# config.net
KiCad netlist of a schematic drawn in Altium Designer
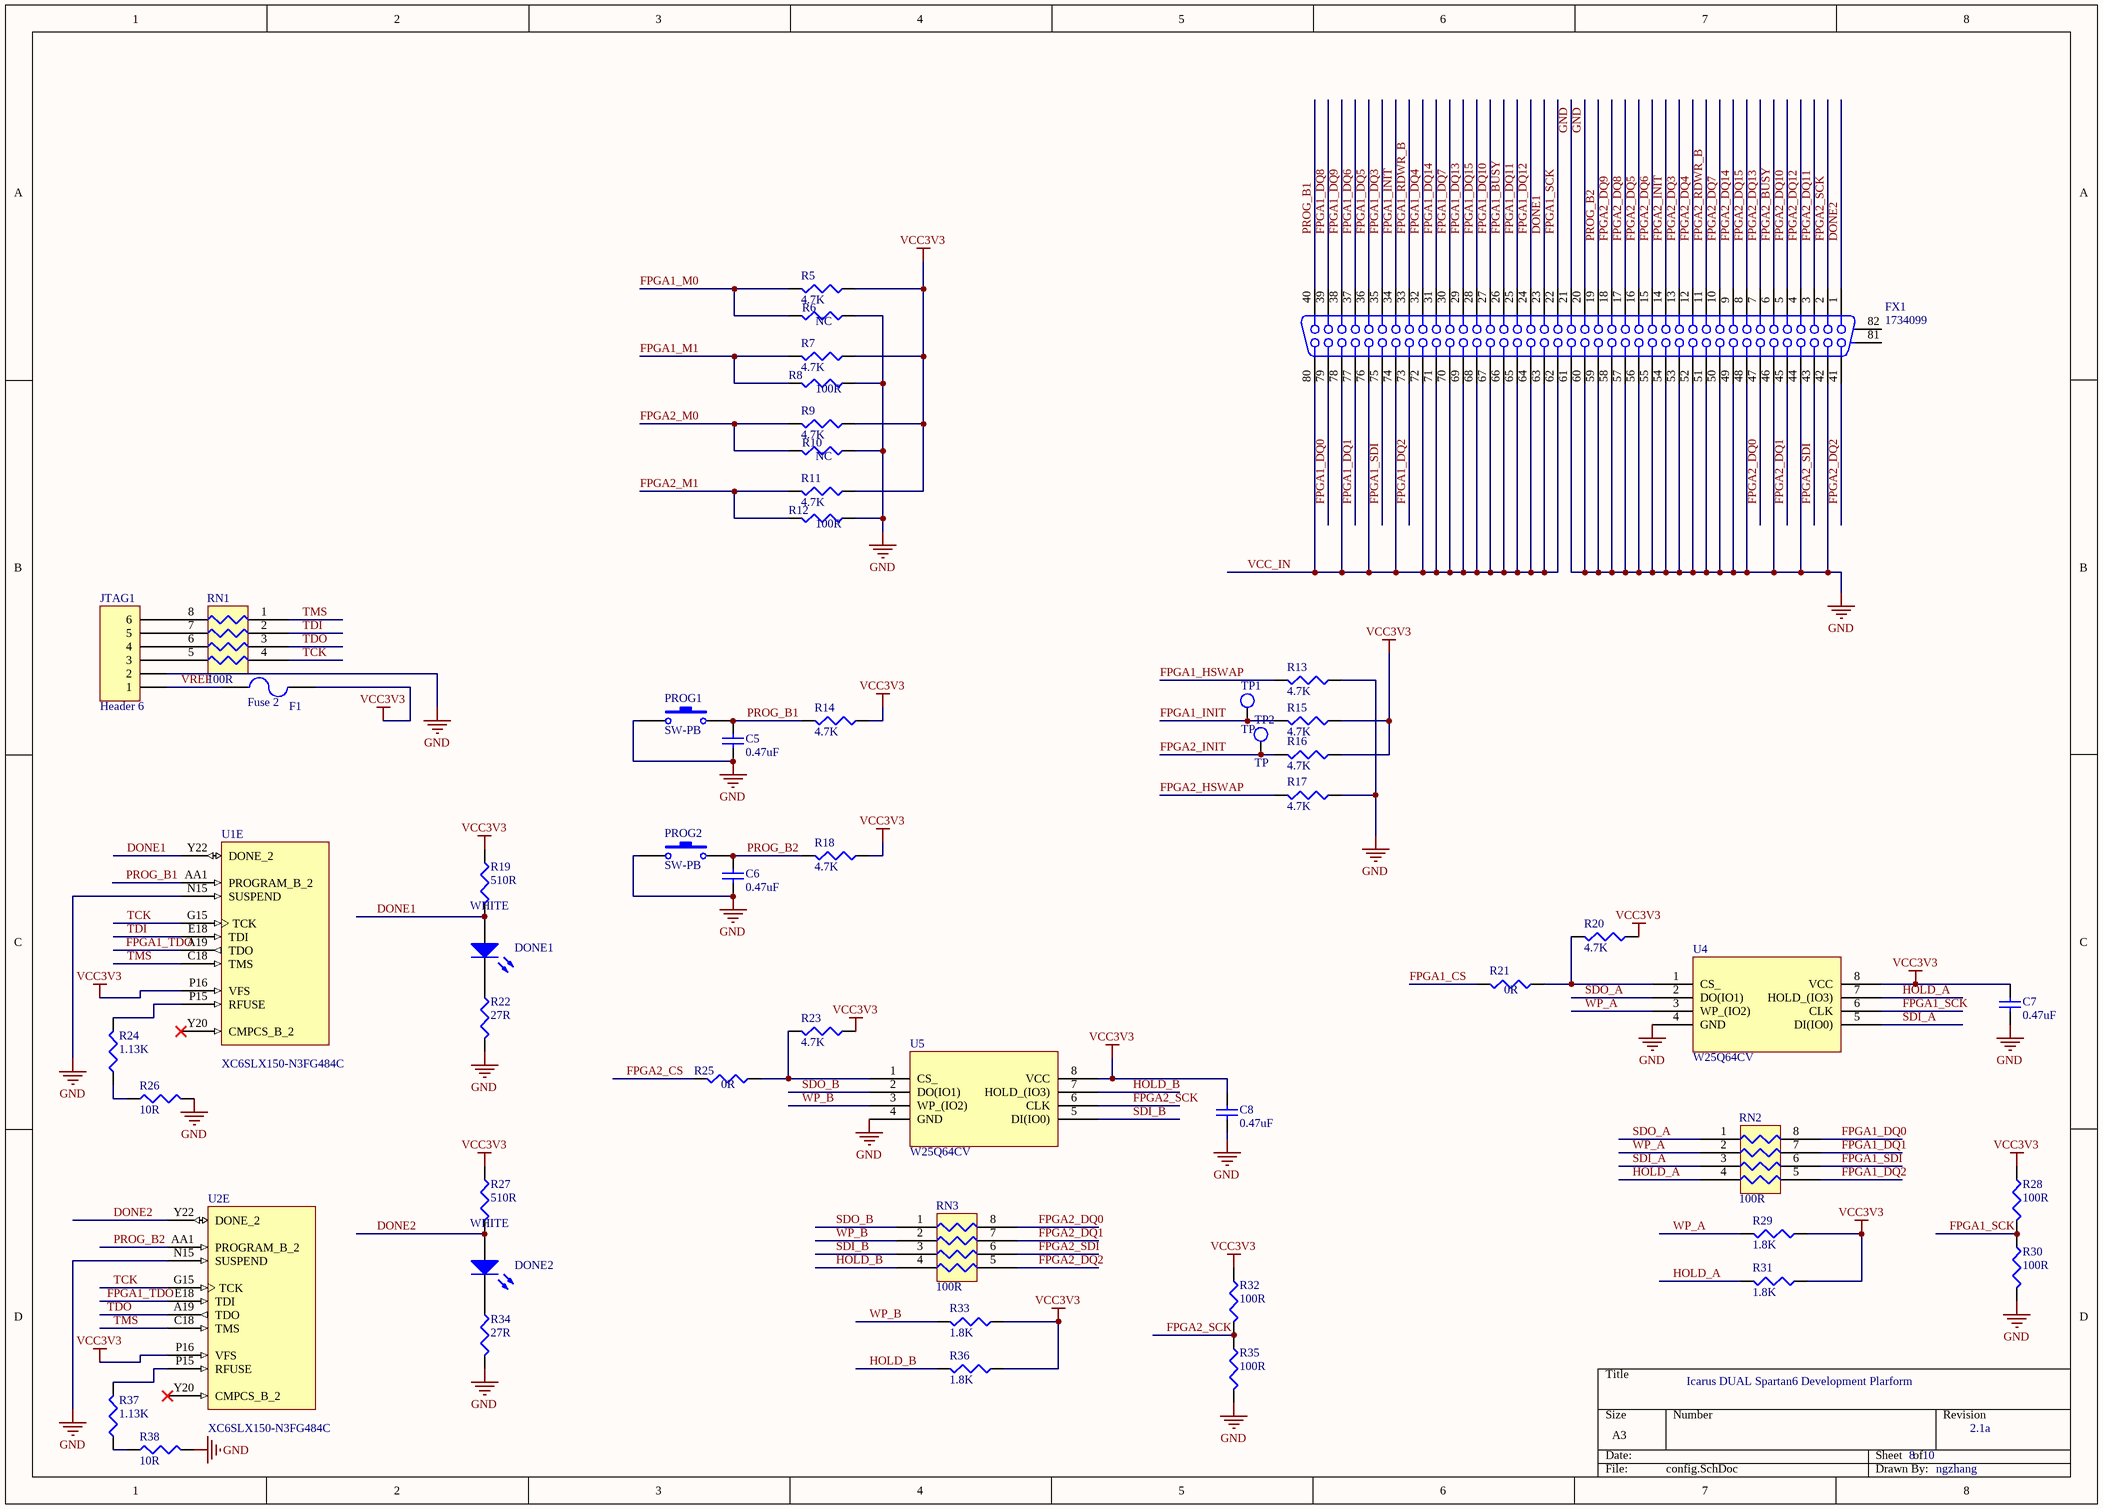
[diagram p0: config.SchDoc]

(export (version "E")
  (design (tool "Eeschema 10.0.6"))
  (components
    (comp (ref "C5")
      (value "0.47uF")
      (footprint "CAPC1005N")
      (description "Capacitor (Semiconductor SIM Model)")
      (fields (field (name "PUBLISHER") "Altium Limited"))
      (libsource (lib "Miscellaneous Devices") (part "Cap Semi"))
    )
    (comp (ref "C6")
      (value "0.47uF")
      (footprint "CAPC1005N")
      (description "Capacitor (Semiconductor SIM Model)")
      (fields (field (name "PUBLISHER") "Altium Limited"))
      (libsource (lib "Miscellaneous Devices") (part "Cap Semi"))
    )
    (comp (ref "C7")
      (value "0.47uF")
      (footprint "CAPC1005N")
      (description "Capacitor (Semiconductor SIM Model)")
      (fields (field (name "PUBLISHER") "Altium Limited"))
      (libsource (lib "Miscellaneous Devices") (part "Cap Semi"))
    )
    (comp (ref "C8")
      (value "0.47uF")
      (footprint "CAPC1005N")
      (description "Capacitor (Semiconductor SIM Model)")
      (fields (field (name "PUBLISHER") "Altium Limited"))
      (libsource (lib "Miscellaneous Devices") (part "Cap Semi"))
    )
    (comp (ref "DONE1")
      (value "WHITE")
      (footprint "CD1608-0603")
      (description "Typical BLUE SiC LED")
      (fields (field (name "PUBLISHER") "Altium Limited"))
      (libsource (lib "Miscellaneous Devices") (part "LED3"))
    )
    (comp (ref "DONE2")
      (value "WHITE")
      (footprint "CD1608-0603")
      (description "Typical BLUE SiC LED")
      (fields (field (name "PUBLISHER") "Altium Limited"))
      (libsource (lib "Miscellaneous Devices") (part "LED3"))
    )
    (comp (ref "F1")
      (value "Fuse 2")
      (footprint "RESC3216N")
      (description "Fuse")
      (fields (field (name "PUBLISHER") "Altium Limited"))
      (libsource (lib "Miscellaneous Devices") (part "Fuse 2"))
    )
    (comp (ref "FX1") (value "1734099") (footprint "1734099") (libsource (lib "S6_2") (part "1734099")))
    (comp (ref "JTAG1")
      (value "Header 6")
      (footprint "HDR1X6")
      (description "Header, 6-Pin")
      (fields (field (name "PUBLISHER") "Altium Limited"))
      (libsource (lib "Miscellaneous Connectors") (part "Header 6"))
    )
    (comp (ref "PROG1")
      (value "SW-PB")
      (footprint "SKQMA")
      (description "Switch")
      (fields (field (name "PUBLISHER") "Altium Limited"))
      (libsource (lib "Miscellaneous Devices") (part "SW-PB"))
    )
    (comp (ref "PROG2")
      (value "SW-PB")
      (footprint "SKQMA")
      (description "Switch")
      (fields (field (name "PUBLISHER") "Altium Limited"))
      (libsource (lib "Miscellaneous Devices") (part "SW-PB"))
    )
    (comp (ref "R5")
      (value "4.7K")
      (footprint "RESC1005N")
      (description "Resistor")
      (fields (field (name "PUBLISHER") "Altium Limited"))
      (libsource (lib "Miscellaneous Devices") (part "Res3"))
    )
    (comp (ref "R6")
      (value "NC")
      (footprint "RESC1005N")
      (description "Resistor")
      (fields (field (name "PUBLISHER") "Altium Limited"))
      (libsource (lib "Miscellaneous Devices") (part "Res3"))
    )
    (comp (ref "R7")
      (value "4.7K")
      (footprint "RESC1005N")
      (description "Resistor")
      (fields (field (name "PUBLISHER") "Altium Limited"))
      (libsource (lib "Miscellaneous Devices") (part "Res3"))
    )
    (comp (ref "R8")
      (value "100R")
      (footprint "RESC1005N")
      (description "Resistor")
      (fields (field (name "PUBLISHER") "Altium Limited"))
      (libsource (lib "Miscellaneous Devices") (part "Res3"))
    )
    (comp (ref "R9")
      (value "4.7K")
      (footprint "RESC1005N")
      (description "Resistor")
      (fields (field (name "PUBLISHER") "Altium Limited"))
      (libsource (lib "Miscellaneous Devices") (part "Res3"))
    )
    (comp (ref "R10")
      (value "NC")
      (footprint "RESC1005N")
      (description "Resistor")
      (fields (field (name "PUBLISHER") "Altium Limited"))
      (libsource (lib "Miscellaneous Devices") (part "Res3"))
    )
    (comp (ref "R11")
      (value "4.7K")
      (footprint "RESC1005N")
      (description "Resistor")
      (fields (field (name "PUBLISHER") "Altium Limited"))
      (libsource (lib "Miscellaneous Devices") (part "Res3"))
    )
    (comp (ref "R12")
      (value "100R")
      (footprint "RESC1005N")
      (description "Resistor")
      (fields (field (name "PUBLISHER") "Altium Limited"))
      (libsource (lib "Miscellaneous Devices") (part "Res3"))
    )
    (comp (ref "R13")
      (value "4.7K")
      (footprint "RESC1005N")
      (description "Resistor")
      (fields (field (name "PUBLISHER") "Altium Limited"))
      (libsource (lib "Miscellaneous Devices") (part "Res3"))
    )
    (comp (ref "R14")
      (value "4.7K")
      (footprint "RESC1005N")
      (description "Resistor")
      (fields (field (name "PUBLISHER") "Altium Limited"))
      (libsource (lib "Miscellaneous Devices") (part "Res3"))
    )
    (comp (ref "R15")
      (value "4.7K")
      (footprint "RESC1005N")
      (description "Resistor")
      (fields (field (name "PUBLISHER") "Altium Limited"))
      (libsource (lib "Miscellaneous Devices") (part "Res3"))
    )
    (comp (ref "R16")
      (value "4.7K")
      (footprint "RESC1005N")
      (description "Resistor")
      (fields (field (name "PUBLISHER") "Altium Limited"))
      (libsource (lib "Miscellaneous Devices") (part "Res3"))
    )
    (comp (ref "R17")
      (value "4.7K")
      (footprint "RESC1005N")
      (description "Resistor")
      (fields (field (name "PUBLISHER") "Altium Limited"))
      (libsource (lib "Miscellaneous Devices") (part "Res3"))
    )
    (comp (ref "R18")
      (value "4.7K")
      (footprint "RESC1005N")
      (description "Resistor")
      (fields (field (name "PUBLISHER") "Altium Limited"))
      (libsource (lib "Miscellaneous Devices") (part "Res3"))
    )
    (comp (ref "R19")
      (value "510R")
      (footprint "RESC1005N")
      (description "Resistor")
      (fields (field (name "PUBLISHER") "Altium Limited"))
      (libsource (lib "Miscellaneous Devices") (part "Res3"))
    )
    (comp (ref "R20")
      (value "4.7K")
      (footprint "RESC1005N")
      (description "Resistor")
      (fields (field (name "PUBLISHER") "Altium Limited"))
      (libsource (lib "Miscellaneous Devices") (part "Res3"))
    )
    (comp (ref "R21")
      (value "0R")
      (footprint "RESC1005N")
      (description "Resistor")
      (fields (field (name "PUBLISHER") "Altium Limited"))
      (libsource (lib "Miscellaneous Devices") (part "Res3"))
    )
    (comp (ref "R22")
      (value "27R")
      (footprint "RESC1005N")
      (description "Resistor")
      (fields (field (name "PUBLISHER") "Altium Limited"))
      (libsource (lib "Miscellaneous Devices") (part "Res3"))
    )
    (comp (ref "R23")
      (value "4.7K")
      (footprint "RESC1005N")
      (description "Resistor")
      (fields (field (name "PUBLISHER") "Altium Limited"))
      (libsource (lib "Miscellaneous Devices") (part "Res3"))
    )
    (comp (ref "R24")
      (value "1.13K")
      (footprint "RESC1608N")
      (description "Resistor")
      (fields (field (name "PUBLISHER") "Altium Limited"))
      (libsource (lib "Miscellaneous Devices") (part "Res3"))
    )
    (comp (ref "R25")
      (value "0R")
      (footprint "RESC1005N")
      (description "Resistor")
      (fields (field (name "PUBLISHER") "Altium Limited"))
      (libsource (lib "Miscellaneous Devices") (part "Res3"))
    )
    (comp (ref "R26")
      (value "10R")
      (footprint "RESC1608N")
      (description "Resistor")
      (fields (field (name "PUBLISHER") "Altium Limited"))
      (libsource (lib "Miscellaneous Devices") (part "Res3"))
    )
    (comp (ref "R27")
      (value "510R")
      (footprint "RESC1005N")
      (description "Resistor")
      (fields (field (name "PUBLISHER") "Altium Limited"))
      (libsource (lib "Miscellaneous Devices") (part "Res3"))
    )
    (comp (ref "R28")
      (value "100R")
      (footprint "RESC1005N")
      (description "Resistor")
      (fields (field (name "PUBLISHER") "Altium Limited"))
      (libsource (lib "Miscellaneous Devices") (part "Res3"))
    )
    (comp (ref "R29")
      (value "1.8K")
      (footprint "RESC1005N")
      (description "Resistor")
      (fields (field (name "PUBLISHER") "Altium Limited"))
      (libsource (lib "Miscellaneous Devices") (part "Res3"))
    )
    (comp (ref "R30")
      (value "100R")
      (footprint "RESC1005N")
      (description "Resistor")
      (fields (field (name "PUBLISHER") "Altium Limited"))
      (libsource (lib "Miscellaneous Devices") (part "Res3"))
    )
    (comp (ref "R31")
      (value "1.8K")
      (footprint "RESC1005N")
      (description "Resistor")
      (fields (field (name "PUBLISHER") "Altium Limited"))
      (libsource (lib "Miscellaneous Devices") (part "Res3"))
    )
    (comp (ref "R32")
      (value "100R")
      (footprint "RESC1005N")
      (description "Resistor")
      (fields (field (name "PUBLISHER") "Altium Limited"))
      (libsource (lib "Miscellaneous Devices") (part "Res3"))
    )
    (comp (ref "R33")
      (value "1.8K")
      (footprint "RESC1005N")
      (description "Resistor")
      (fields (field (name "PUBLISHER") "Altium Limited"))
      (libsource (lib "Miscellaneous Devices") (part "Res3"))
    )
    (comp (ref "R34")
      (value "27R")
      (footprint "RESC1005N")
      (description "Resistor")
      (fields (field (name "PUBLISHER") "Altium Limited"))
      (libsource (lib "Miscellaneous Devices") (part "Res3"))
    )
    (comp (ref "R35")
      (value "100R")
      (footprint "RESC1005N")
      (description "Resistor")
      (fields (field (name "PUBLISHER") "Altium Limited"))
      (libsource (lib "Miscellaneous Devices") (part "Res3"))
    )
    (comp (ref "R36")
      (value "1.8K")
      (footprint "RESC1005N")
      (description "Resistor")
      (fields (field (name "PUBLISHER") "Altium Limited"))
      (libsource (lib "Miscellaneous Devices") (part "Res3"))
    )
    (comp (ref "R37")
      (value "1.13K")
      (footprint "RESC1608N")
      (description "Resistor")
      (fields (field (name "PUBLISHER") "Altium Limited"))
      (libsource (lib "Miscellaneous Devices") (part "Res3"))
    )
    (comp (ref "R38")
      (value "10R")
      (footprint "RESC1608N")
      (description "Resistor")
      (fields (field (name "PUBLISHER") "Altium Limited"))
      (libsource (lib "Miscellaneous Devices") (part "Res3"))
    )
    (comp (ref "RN1") (value "100R") (footprint "EXBV8V") (libsource (lib "") (part "RES4PACK_1")))
    (comp (ref "RN2") (value "100R") (footprint "EXBV8V") (libsource (lib "S6") (part "RES4PACK")))
    (comp (ref "RN3") (value "100R") (footprint "EXBV8V") (libsource (lib "S6") (part "RES4PACK")))
    (comp (ref "TP1") (value "TP") (footprint "TP") (libsource (lib "S6") (part "TP")))
    (comp (ref "TP2") (value "TP") (footprint "TP") (libsource (lib "S6") (part "TP")))
    (comp (ref "U1")
      (value "XC6SLX150-N3FG484C")
      (footprint "FG484")
      (fields (field (name "PUBLISHER") "Altium Limited"))
      (libsource (lib "Xilinx Spartan-6") (part "XC6SLX150-N3FG484C"))
    )
    (comp (ref "U2")
      (value "XC6SLX150-N3FG484C")
      (footprint "FG484")
      (fields (field (name "PUBLISHER") "Altium Limited"))
      (libsource (lib "Xilinx Spartan-6") (part "XC6SLX150-N3FG484C"))
    )
    (comp (ref "U4") (value "W25Q64CV") (footprint "WSOP8") (libsource (lib "S6") (part "W25Q64CV")))
    (comp (ref "U5") (value "W25Q64CV") (footprint "WSOP8") (libsource (lib "S6") (part "W25Q64CV")))
  )
  (nets
    (net (code "1") (name "/DONE1") (class "Default")
      (node (ref "DONE1") (pin "1") (pinfunction "A_1") (pintype "passive"))
      (node (ref "FX1") (pin "23") (pinfunction "23_23") (pintype "passive"))
      (node (ref "R19") (pin "2") (pinfunction "2_2") (pintype "passive"))
      (node (ref "U1") (pin "Y22") (pinfunction "DONE_2_Y22") (pintype "bidirectional"))
    )
    (net (code "2") (name "/DONE2") (class "Default")
      (node (ref "DONE2") (pin "1") (pinfunction "A_1") (pintype "passive"))
      (node (ref "FX1") (pin "1") (pinfunction "1_1") (pintype "passive"))
      (node (ref "R27") (pin "2") (pinfunction "2_2") (pintype "passive"))
      (node (ref "U2") (pin "Y22") (pinfunction "DONE_2_Y22") (pintype "bidirectional"))
    )
    (net (code "3") (name "/FPGA1_BUSY") (class "Default")
      (node (ref "FX1") (pin "26") (pinfunction "26_26") (pintype "passive"))
    )
    (net (code "4") (name "/FPGA1_CS") (class "Default")
      (node (ref "R21") (pin "2") (pinfunction "2_2") (pintype "passive"))
    )
    (net (code "5") (name "/FPGA1_DQ0") (class "Default")
      (node (ref "FX1") (pin "79") (pinfunction "79_79") (pintype "passive"))
      (node (ref "RN2") (pin "8") (pinfunction "8_8") (pintype "power_in"))
    )
    (net (code "6") (name "/FPGA1_DQ1") (class "Default")
      (node (ref "FX1") (pin "77") (pinfunction "77_77") (pintype "passive"))
      (node (ref "RN2") (pin "7") (pinfunction "7_7") (pintype "power_in"))
    )
    (net (code "7") (name "/FPGA1_DQ2") (class "Default")
      (node (ref "FX1") (pin "73") (pinfunction "73_73") (pintype "passive"))
      (node (ref "RN2") (pin "5") (pinfunction "5_5") (pintype "power_in"))
    )
    (net (code "8") (name "/FPGA1_DQ3") (class "Default")
      (node (ref "FX1") (pin "35") (pinfunction "35_35") (pintype "passive"))
    )
    (net (code "9") (name "/FPGA1_DQ4") (class "Default")
      (node (ref "FX1") (pin "32") (pinfunction "32_32") (pintype "passive"))
    )
    (net (code "10") (name "/FPGA1_DQ5") (class "Default")
      (node (ref "FX1") (pin "36") (pinfunction "36_36") (pintype "passive"))
    )
    (net (code "11") (name "/FPGA1_DQ6") (class "Default")
      (node (ref "FX1") (pin "37") (pinfunction "37_37") (pintype "passive"))
    )
    (net (code "12") (name "/FPGA1_DQ7") (class "Default")
      (node (ref "FX1") (pin "30") (pinfunction "30_30") (pintype "passive"))
    )
    (net (code "13") (name "/FPGA1_DQ8") (class "Default")
      (node (ref "FX1") (pin "39") (pinfunction "39_39") (pintype "passive"))
    )
    (net (code "14") (name "/FPGA1_DQ9") (class "Default")
      (node (ref "FX1") (pin "38") (pinfunction "38_38") (pintype "passive"))
    )
    (net (code "15") (name "/FPGA1_DQ10") (class "Default")
      (node (ref "FX1") (pin "27") (pinfunction "27_27") (pintype "passive"))
    )
    (net (code "16") (name "/FPGA1_DQ11") (class "Default")
      (node (ref "FX1") (pin "25") (pinfunction "25_25") (pintype "passive"))
    )
    (net (code "17") (name "/FPGA1_DQ12") (class "Default")
      (node (ref "FX1") (pin "24") (pinfunction "24_24") (pintype "passive"))
    )
    (net (code "18") (name "/FPGA1_DQ13") (class "Default")
      (node (ref "FX1") (pin "29") (pinfunction "29_29") (pintype "passive"))
    )
    (net (code "19") (name "/FPGA1_DQ14") (class "Default")
      (node (ref "FX1") (pin "31") (pinfunction "31_31") (pintype "passive"))
    )
    (net (code "20") (name "/FPGA1_DQ15") (class "Default")
      (node (ref "FX1") (pin "28") (pinfunction "28_28") (pintype "passive"))
    )
    (net (code "21") (name "/FPGA1_HSWAP") (class "Default")
      (node (ref "R13") (pin "2") (pinfunction "2_2") (pintype "passive"))
    )
    (net (code "22") (name "/FPGA1_INIT") (class "Default")
      (node (ref "FX1") (pin "34") (pinfunction "34_34") (pintype "passive"))
      (node (ref "R15") (pin "2") (pinfunction "2_2") (pintype "passive"))
      (node (ref "TP1") (pin "1") (pinfunction "TP_1") (pintype "passive"))
    )
    (net (code "23") (name "/FPGA1_M0") (class "Default")
      (node (ref "R5") (pin "2") (pinfunction "2_2") (pintype "passive"))
      (node (ref "R6") (pin "2") (pinfunction "2_2") (pintype "passive"))
    )
    (net (code "24") (name "/FPGA1_M1") (class "Default")
      (node (ref "R7") (pin "2") (pinfunction "2_2") (pintype "passive"))
      (node (ref "R8") (pin "2") (pinfunction "2_2") (pintype "passive"))
    )
    (net (code "25") (name "/FPGA1_RDWR_B") (class "Default")
      (node (ref "FX1") (pin "33") (pinfunction "33_33") (pintype "passive"))
    )
    (net (code "26") (name "/FPGA1_SCK") (class "Default")
      (node (ref "FX1") (pin "22") (pinfunction "22_22") (pintype "passive"))
      (node (ref "R28") (pin "2") (pinfunction "2_2") (pintype "passive"))
      (node (ref "R30") (pin "1") (pinfunction "1_1") (pintype "passive"))
      (node (ref "U4") (pin "6") (pinfunction "CLK_6") (pintype "passive"))
    )
    (net (code "27") (name "/FPGA1_SDI") (class "Default")
      (node (ref "FX1") (pin "75") (pinfunction "75_75") (pintype "passive"))
      (node (ref "RN2") (pin "6") (pinfunction "6_6") (pintype "power_in"))
    )
    (net (code "28") (name "/FPGA1_TDO") (class "Default")
      (node (ref "U1") (pin "A19") (pinfunction "TDO_A19") (pintype "output"))
      (node (ref "U2") (pin "E18") (pinfunction "TDI_E18") (pintype "input"))
    )
    (net (code "29") (name "/FPGA2_BUSY") (class "Default")
      (node (ref "FX1") (pin "6") (pinfunction "6_6") (pintype "passive"))
    )
    (net (code "30") (name "/FPGA2_CS") (class "Default")
      (node (ref "R25") (pin "2") (pinfunction "2_2") (pintype "passive"))
    )
    (net (code "31") (name "/FPGA2_DQ0") (class "Default")
      (node (ref "FX1") (pin "47") (pinfunction "47_47") (pintype "passive"))
      (node (ref "RN3") (pin "8") (pinfunction "8_8") (pintype "power_in"))
    )
    (net (code "32") (name "/FPGA2_DQ1") (class "Default")
      (node (ref "FX1") (pin "45") (pinfunction "45_45") (pintype "passive"))
      (node (ref "RN3") (pin "7") (pinfunction "7_7") (pintype "power_in"))
    )
    (net (code "33") (name "/FPGA2_DQ2") (class "Default")
      (node (ref "FX1") (pin "41") (pinfunction "41_41") (pintype "passive"))
      (node (ref "RN3") (pin "5") (pinfunction "5_5") (pintype "power_in"))
    )
    (net (code "34") (name "/FPGA2_DQ3") (class "Default")
      (node (ref "FX1") (pin "13") (pinfunction "13_13") (pintype "passive"))
    )
    (net (code "35") (name "/FPGA2_DQ4") (class "Default")
      (node (ref "FX1") (pin "12") (pinfunction "12_12") (pintype "passive"))
    )
    (net (code "36") (name "/FPGA2_DQ5") (class "Default")
      (node (ref "FX1") (pin "16") (pinfunction "16_16") (pintype "passive"))
    )
    (net (code "37") (name "/FPGA2_DQ6") (class "Default")
      (node (ref "FX1") (pin "15") (pinfunction "15_15") (pintype "passive"))
    )
    (net (code "38") (name "/FPGA2_DQ7") (class "Default")
      (node (ref "FX1") (pin "10") (pinfunction "10_10") (pintype "passive"))
    )
    (net (code "39") (name "/FPGA2_DQ8") (class "Default")
      (node (ref "FX1") (pin "17") (pinfunction "17_17") (pintype "passive"))
    )
    (net (code "40") (name "/FPGA2_DQ9") (class "Default")
      (node (ref "FX1") (pin "18") (pinfunction "18_18") (pintype "passive"))
    )
    (net (code "41") (name "/FPGA2_DQ10") (class "Default")
      (node (ref "FX1") (pin "5") (pinfunction "5_5") (pintype "passive"))
    )
    (net (code "42") (name "/FPGA2_DQ11") (class "Default")
      (node (ref "FX1") (pin "3") (pinfunction "3_3") (pintype "passive"))
    )
    (net (code "43") (name "/FPGA2_DQ12") (class "Default")
      (node (ref "FX1") (pin "4") (pinfunction "4_4") (pintype "passive"))
    )
    (net (code "44") (name "/FPGA2_DQ13") (class "Default")
      (node (ref "FX1") (pin "7") (pinfunction "7_7") (pintype "passive"))
    )
    (net (code "45") (name "/FPGA2_DQ14") (class "Default")
      (node (ref "FX1") (pin "9") (pinfunction "9_9") (pintype "passive"))
    )
    (net (code "46") (name "/FPGA2_DQ15") (class "Default")
      (node (ref "FX1") (pin "8") (pinfunction "8_8") (pintype "passive"))
    )
    (net (code "47") (name "/FPGA2_HSWAP") (class "Default")
      (node (ref "R17") (pin "2") (pinfunction "2_2") (pintype "passive"))
    )
    (net (code "48") (name "/FPGA2_INIT") (class "Default")
      (node (ref "FX1") (pin "14") (pinfunction "14_14") (pintype "passive"))
      (node (ref "R16") (pin "2") (pinfunction "2_2") (pintype "passive"))
      (node (ref "TP2") (pin "1") (pinfunction "TP_1") (pintype "passive"))
    )
    (net (code "49") (name "/FPGA2_M0") (class "Default")
      (node (ref "R10") (pin "2") (pinfunction "2_2") (pintype "passive"))
      (node (ref "R9") (pin "2") (pinfunction "2_2") (pintype "passive"))
    )
    (net (code "50") (name "/FPGA2_M1") (class "Default")
      (node (ref "R11") (pin "2") (pinfunction "2_2") (pintype "passive"))
      (node (ref "R12") (pin "2") (pinfunction "2_2") (pintype "passive"))
    )
    (net (code "51") (name "/FPGA2_RDWR_B") (class "Default")
      (node (ref "FX1") (pin "11") (pinfunction "11_11") (pintype "passive"))
    )
    (net (code "52") (name "/FPGA2_SCK") (class "Default")
      (node (ref "FX1") (pin "2") (pinfunction "2_2") (pintype "passive"))
      (node (ref "R32") (pin "2") (pinfunction "2_2") (pintype "passive"))
      (node (ref "R35") (pin "1") (pinfunction "1_1") (pintype "passive"))
      (node (ref "U5") (pin "6") (pinfunction "CLK_6") (pintype "passive"))
    )
    (net (code "53") (name "/FPGA2_SDI") (class "Default")
      (node (ref "FX1") (pin "43") (pinfunction "43_43") (pintype "passive"))
      (node (ref "RN3") (pin "6") (pinfunction "6_6") (pintype "power_in"))
    )
    (net (code "54") (name "/HOLD_A") (class "Default")
      (node (ref "R31") (pin "2") (pinfunction "2_2") (pintype "passive"))
      (node (ref "RN2") (pin "4") (pinfunction "4_4") (pintype "power_in"))
      (node (ref "U4") (pin "7") (pinfunction "HOLD_(IO3)_7") (pintype "passive"))
    )
    (net (code "55") (name "/HOLD_B") (class "Default")
      (node (ref "R36") (pin "2") (pinfunction "2_2") (pintype "passive"))
      (node (ref "RN3") (pin "4") (pinfunction "4_4") (pintype "power_in"))
      (node (ref "U5") (pin "7") (pinfunction "HOLD_(IO3)_7") (pintype "passive"))
    )
    (net (code "56") (name "/PROG_B1") (class "Default")
      (node (ref "C5") (pin "1") (pinfunction "1_1") (pintype "passive"))
      (node (ref "FX1") (pin "40") (pinfunction "40_40") (pintype "passive"))
      (node (ref "PROG1") (pin "2") (pinfunction "2_2") (pintype "passive"))
      (node (ref "R14") (pin "2") (pinfunction "2_2") (pintype "passive"))
      (node (ref "U1") (pin "AA1") (pinfunction "PROGRAM_B_2_AA1") (pintype "input"))
    )
    (net (code "57") (name "/PROG_B2") (class "Default")
      (node (ref "C6") (pin "1") (pinfunction "1_1") (pintype "passive"))
      (node (ref "FX1") (pin "19") (pinfunction "19_19") (pintype "passive"))
      (node (ref "PROG2") (pin "2") (pinfunction "2_2") (pintype "passive"))
      (node (ref "R18") (pin "2") (pinfunction "2_2") (pintype "passive"))
      (node (ref "U2") (pin "AA1") (pinfunction "PROGRAM_B_2_AA1") (pintype "input"))
    )
    (net (code "58") (name "/SDI_A") (class "Default")
      (node (ref "RN2") (pin "3") (pinfunction "3_3") (pintype "power_in"))
      (node (ref "U4") (pin "5") (pinfunction "DI(IO0)_5") (pintype "passive"))
    )
    (net (code "59") (name "/SDI_B") (class "Default")
      (node (ref "RN3") (pin "3") (pinfunction "3_3") (pintype "power_in"))
      (node (ref "U5") (pin "5") (pinfunction "DI(IO0)_5") (pintype "passive"))
    )
    (net (code "60") (name "/SDO_A") (class "Default")
      (node (ref "RN2") (pin "1") (pinfunction "1_1") (pintype "power_in"))
      (node (ref "U4") (pin "2") (pinfunction "DO(IO1)_2") (pintype "passive"))
    )
    (net (code "61") (name "/SDO_B") (class "Default")
      (node (ref "RN3") (pin "1") (pinfunction "1_1") (pintype "power_in"))
      (node (ref "U5") (pin "2") (pinfunction "DO(IO1)_2") (pintype "passive"))
    )
    (net (code "62") (name "/TCK") (class "Default")
      (node (ref "RN1") (pin "4") (pinfunction "4_4") (pintype "power_in"))
      (node (ref "U1") (pin "G15") (pinfunction "TCK_G15") (pintype "input"))
      (node (ref "U2") (pin "G15") (pinfunction "TCK_G15") (pintype "input"))
    )
    (net (code "63") (name "/TDI") (class "Default")
      (node (ref "RN1") (pin "2") (pinfunction "2_2") (pintype "power_in"))
      (node (ref "U1") (pin "E18") (pinfunction "TDI_E18") (pintype "input"))
    )
    (net (code "64") (name "/TDO") (class "Default")
      (node (ref "RN1") (pin "3") (pinfunction "3_3") (pintype "power_in"))
      (node (ref "U2") (pin "A19") (pinfunction "TDO_A19") (pintype "output"))
    )
    (net (code "65") (name "/TMS") (class "Default")
      (node (ref "RN1") (pin "1") (pinfunction "1_1") (pintype "power_in"))
      (node (ref "U1") (pin "C18") (pinfunction "TMS_C18") (pintype "input"))
      (node (ref "U2") (pin "C18") (pinfunction "TMS_C18") (pintype "input"))
    )
    (net (code "66") (name "/VCC_IN") (class "Default")
      (node (ref "FX1") (pin "62") (pinfunction "62_62") (pintype "passive"))
      (node (ref "FX1") (pin "63") (pinfunction "63_63") (pintype "passive"))
      (node (ref "FX1") (pin "64") (pinfunction "64_64") (pintype "passive"))
      (node (ref "FX1") (pin "65") (pinfunction "65_65") (pintype "passive"))
      (node (ref "FX1") (pin "66") (pinfunction "66_66") (pintype "passive"))
      (node (ref "FX1") (pin "67") (pinfunction "67_67") (pintype "passive"))
      (node (ref "FX1") (pin "68") (pinfunction "68_68") (pintype "passive"))
      (node (ref "FX1") (pin "69") (pinfunction "69_69") (pintype "passive"))
      (node (ref "FX1") (pin "70") (pinfunction "70_70") (pintype "passive"))
      (node (ref "FX1") (pin "71") (pinfunction "71_71") (pintype "passive"))
      (node (ref "FX1") (pin "72") (pinfunction "72_72") (pintype "passive"))
      (node (ref "FX1") (pin "74") (pinfunction "74_74") (pintype "passive"))
      (node (ref "FX1") (pin "76") (pinfunction "76_76") (pintype "passive"))
      (node (ref "FX1") (pin "78") (pinfunction "78_78") (pintype "passive"))
      (node (ref "FX1") (pin "80") (pinfunction "80_80") (pintype "passive"))
    )
    (net (code "67") (name "/VREF") (class "Default")
      (node (ref "F1") (pin "1") (pinfunction "1_1") (pintype "passive"))
      (node (ref "JTAG1") (pin "1") (pinfunction "1_1") (pintype "passive"))
    )
    (net (code "68") (name "/WP_A") (class "Default")
      (node (ref "R29") (pin "2") (pinfunction "2_2") (pintype "passive"))
      (node (ref "RN2") (pin "2") (pinfunction "2_2") (pintype "power_in"))
      (node (ref "U4") (pin "3") (pinfunction "WP_(IO2)_3") (pintype "passive"))
    )
    (net (code "69") (name "/WP_B") (class "Default")
      (node (ref "R33") (pin "2") (pinfunction "2_2") (pintype "passive"))
      (node (ref "RN3") (pin "2") (pinfunction "2_2") (pintype "power_in"))
      (node (ref "U5") (pin "3") (pinfunction "WP_(IO2)_3") (pintype "passive"))
    )
    (net (code "70") (name "GND") (class "Default")
      (node (ref "C5") (pin "2") (pinfunction "2_2") (pintype "passive"))
      (node (ref "C6") (pin "2") (pinfunction "2_2") (pintype "passive"))
      (node (ref "C7") (pin "1") (pinfunction "1_1") (pintype "passive"))
      (node (ref "C8") (pin "1") (pinfunction "1_1") (pintype "passive"))
      (node (ref "FX1") (pin "20") (pinfunction "20_20") (pintype "passive"))
      (node (ref "FX1") (pin "21") (pinfunction "21_21") (pintype "passive"))
      (node (ref "FX1") (pin "42") (pinfunction "42_42") (pintype "passive"))
      (node (ref "FX1") (pin "44") (pinfunction "44_44") (pintype "passive"))
      (node (ref "FX1") (pin "46") (pinfunction "46_46") (pintype "passive"))
      (node (ref "FX1") (pin "48") (pinfunction "48_48") (pintype "passive"))
      (node (ref "FX1") (pin "49") (pinfunction "49_49") (pintype "passive"))
      (node (ref "FX1") (pin "50") (pinfunction "50_50") (pintype "passive"))
      (node (ref "FX1") (pin "51") (pinfunction "51_51") (pintype "passive"))
      (node (ref "FX1") (pin "52") (pinfunction "52_52") (pintype "passive"))
      (node (ref "FX1") (pin "53") (pinfunction "53_53") (pintype "passive"))
      (node (ref "FX1") (pin "54") (pinfunction "54_54") (pintype "passive"))
      (node (ref "FX1") (pin "55") (pinfunction "55_55") (pintype "passive"))
      (node (ref "FX1") (pin "56") (pinfunction "56_56") (pintype "passive"))
      (node (ref "FX1") (pin "57") (pinfunction "57_57") (pintype "passive"))
      (node (ref "FX1") (pin "58") (pinfunction "58_58") (pintype "passive"))
      (node (ref "FX1") (pin "59") (pinfunction "59_59") (pintype "passive"))
      (node (ref "FX1") (pin "60") (pinfunction "60_60") (pintype "passive"))
      (node (ref "FX1") (pin "61") (pinfunction "61_61") (pintype "passive"))
      (node (ref "JTAG1") (pin "2") (pinfunction "2_2") (pintype "passive"))
      (node (ref "PROG1") (pin "1") (pinfunction "1_1") (pintype "passive"))
      (node (ref "PROG2") (pin "1") (pinfunction "1_1") (pintype "passive"))
      (node (ref "R10") (pin "1") (pinfunction "1_1") (pintype "passive"))
      (node (ref "R12") (pin "1") (pinfunction "1_1") (pintype "passive"))
      (node (ref "R13") (pin "1") (pinfunction "1_1") (pintype "passive"))
      (node (ref "R17") (pin "1") (pinfunction "1_1") (pintype "passive"))
      (node (ref "R22") (pin "2") (pinfunction "2_2") (pintype "passive"))
      (node (ref "R26") (pin "2") (pinfunction "2_2") (pintype "passive"))
      (node (ref "R30") (pin "2") (pinfunction "2_2") (pintype "passive"))
      (node (ref "R34") (pin "2") (pinfunction "2_2") (pintype "passive"))
      (node (ref "R35") (pin "2") (pinfunction "2_2") (pintype "passive"))
      (node (ref "R38") (pin "2") (pinfunction "2_2") (pintype "passive"))
      (node (ref "R6") (pin "1") (pinfunction "1_1") (pintype "passive"))
      (node (ref "R8") (pin "1") (pinfunction "1_1") (pintype "passive"))
      (node (ref "U1") (pin "N15") (pinfunction "SUSPEND_N15") (pintype "input"))
      (node (ref "U2") (pin "N15") (pinfunction "SUSPEND_N15") (pintype "input"))
      (node (ref "U4") (pin "4") (pinfunction "GND_4") (pintype "passive"))
      (node (ref "U5") (pin "4") (pinfunction "GND_4") (pintype "passive"))
    )
    (net (code "71") (name "Net-(DONE1-K)") (class "Default")
      (node (ref "DONE1") (pin "2") (pinfunction "K_2") (pintype "passive"))
      (node (ref "R22") (pin "1") (pinfunction "1_1") (pintype "passive"))
    )
    (net (code "72") (name "Net-(DONE2-K)") (class "Default")
      (node (ref "DONE2") (pin "2") (pinfunction "K_2") (pintype "passive"))
      (node (ref "R34") (pin "1") (pinfunction "1_1") (pintype "passive"))
    )
    (net (code "73") (name "Net-(JTAG1-Pad3)") (class "Default")
      (node (ref "JTAG1") (pin "3") (pinfunction "3_3") (pintype "passive"))
      (node (ref "RN1") (pin "5") (pinfunction "5_5") (pintype "power_in"))
    )
    (net (code "74") (name "Net-(JTAG1-Pad4)") (class "Default")
      (node (ref "JTAG1") (pin "4") (pinfunction "4_4") (pintype "passive"))
      (node (ref "RN1") (pin "6") (pinfunction "6_6") (pintype "power_in"))
    )
    (net (code "75") (name "Net-(JTAG1-Pad5)") (class "Default")
      (node (ref "JTAG1") (pin "5") (pinfunction "5_5") (pintype "passive"))
      (node (ref "RN1") (pin "7") (pinfunction "7_7") (pintype "power_in"))
    )
    (net (code "76") (name "Net-(JTAG1-Pad6)") (class "Default")
      (node (ref "JTAG1") (pin "6") (pinfunction "6_6") (pintype "passive"))
      (node (ref "RN1") (pin "8") (pinfunction "8_8") (pintype "power_in"))
    )
    (net (code "77") (name "Net-(R24-Pad1)") (class "Default")
      (node (ref "R24") (pin "1") (pinfunction "1_1") (pintype "passive"))
      (node (ref "R26") (pin "1") (pinfunction "1_1") (pintype "passive"))
    )
    (net (code "78") (name "Net-(R37-Pad1)") (class "Default")
      (node (ref "R37") (pin "1") (pinfunction "1_1") (pintype "passive"))
      (node (ref "R38") (pin "1") (pinfunction "1_1") (pintype "passive"))
    )
    (net (code "79") (name "Net-(U1E-RFUSE)") (class "Default")
      (node (ref "R24") (pin "2") (pinfunction "2_2") (pintype "passive"))
      (node (ref "U1") (pin "P15") (pinfunction "RFUSE_P15") (pintype "input"))
    )
    (net (code "80") (name "Net-(U2E-RFUSE)") (class "Default")
      (node (ref "R37") (pin "2") (pinfunction "2_2") (pintype "passive"))
      (node (ref "U2") (pin "P15") (pinfunction "RFUSE_P15") (pintype "input"))
    )
    (net (code "81") (name "Net-(U4-CS_)") (class "Default")
      (node (ref "R20") (pin "2") (pinfunction "2_2") (pintype "passive"))
      (node (ref "R21") (pin "1") (pinfunction "1_1") (pintype "passive"))
      (node (ref "U4") (pin "1") (pinfunction "CS__1") (pintype "passive"))
    )
    (net (code "82") (name "Net-(U5-CS_)") (class "Default")
      (node (ref "R23") (pin "2") (pinfunction "2_2") (pintype "passive"))
      (node (ref "R25") (pin "1") (pinfunction "1_1") (pintype "passive"))
      (node (ref "U5") (pin "1") (pinfunction "CS__1") (pintype "passive"))
    )
    (net (code "83") (name "VCC3V3") (class "Default")
      (node (ref "C7") (pin "2") (pinfunction "2_2") (pintype "passive"))
      (node (ref "C8") (pin "2") (pinfunction "2_2") (pintype "passive"))
      (node (ref "F1") (pin "2") (pinfunction "2_2") (pintype "passive"))
      (node (ref "R11") (pin "1") (pinfunction "1_1") (pintype "passive"))
      (node (ref "R14") (pin "1") (pinfunction "1_1") (pintype "passive"))
      (node (ref "R15") (pin "1") (pinfunction "1_1") (pintype "passive"))
      (node (ref "R16") (pin "1") (pinfunction "1_1") (pintype "passive"))
      (node (ref "R18") (pin "1") (pinfunction "1_1") (pintype "passive"))
      (node (ref "R19") (pin "1") (pinfunction "1_1") (pintype "passive"))
      (node (ref "R20") (pin "1") (pinfunction "1_1") (pintype "passive"))
      (node (ref "R23") (pin "1") (pinfunction "1_1") (pintype "passive"))
      (node (ref "R27") (pin "1") (pinfunction "1_1") (pintype "passive"))
      (node (ref "R28") (pin "1") (pinfunction "1_1") (pintype "passive"))
      (node (ref "R29") (pin "1") (pinfunction "1_1") (pintype "passive"))
      (node (ref "R31") (pin "1") (pinfunction "1_1") (pintype "passive"))
      (node (ref "R32") (pin "1") (pinfunction "1_1") (pintype "passive"))
      (node (ref "R33") (pin "1") (pinfunction "1_1") (pintype "passive"))
      (node (ref "R36") (pin "1") (pinfunction "1_1") (pintype "passive"))
      (node (ref "R5") (pin "1") (pinfunction "1_1") (pintype "passive"))
      (node (ref "R7") (pin "1") (pinfunction "1_1") (pintype "passive"))
      (node (ref "R9") (pin "1") (pinfunction "1_1") (pintype "passive"))
      (node (ref "U1") (pin "P16") (pinfunction "VFS_P16") (pintype "input"))
      (node (ref "U2") (pin "P16") (pinfunction "VFS_P16") (pintype "input"))
      (node (ref "U4") (pin "8") (pinfunction "VCC_8") (pintype "passive"))
      (node (ref "U5") (pin "8") (pinfunction "VCC_8") (pintype "passive"))
    )
    (net (code "84") (name "unconnected-(FX1-MH1-Pad81)") (class "Default")
      (node (ref "FX1") (pin "81") (pinfunction "MH1_81") (pintype "passive"))
    )
    (net (code "85") (name "unconnected-(FX1-MH2-Pad82)") (class "Default")
      (node (ref "FX1") (pin "82") (pinfunction "MH2_82") (pintype "passive"))
    )
    (net (code "86") (name "unconnected-(U1E-CMPCS_B_2-PadY20)") (class "Default")
      (node (ref "U1") (pin "Y20") (pinfunction "CMPCS_B_2_Y20") (pintype "input+no_connect"))
    )
    (net (code "87") (name "unconnected-(U2E-CMPCS_B_2-PadY20)") (class "Default")
      (node (ref "U2") (pin "Y20") (pinfunction "CMPCS_B_2_Y20") (pintype "input+no_connect"))
    )
  )
)
